# H0ARAx_Backend.net
KiCad netlist of a schematic drawn in Altium Designer
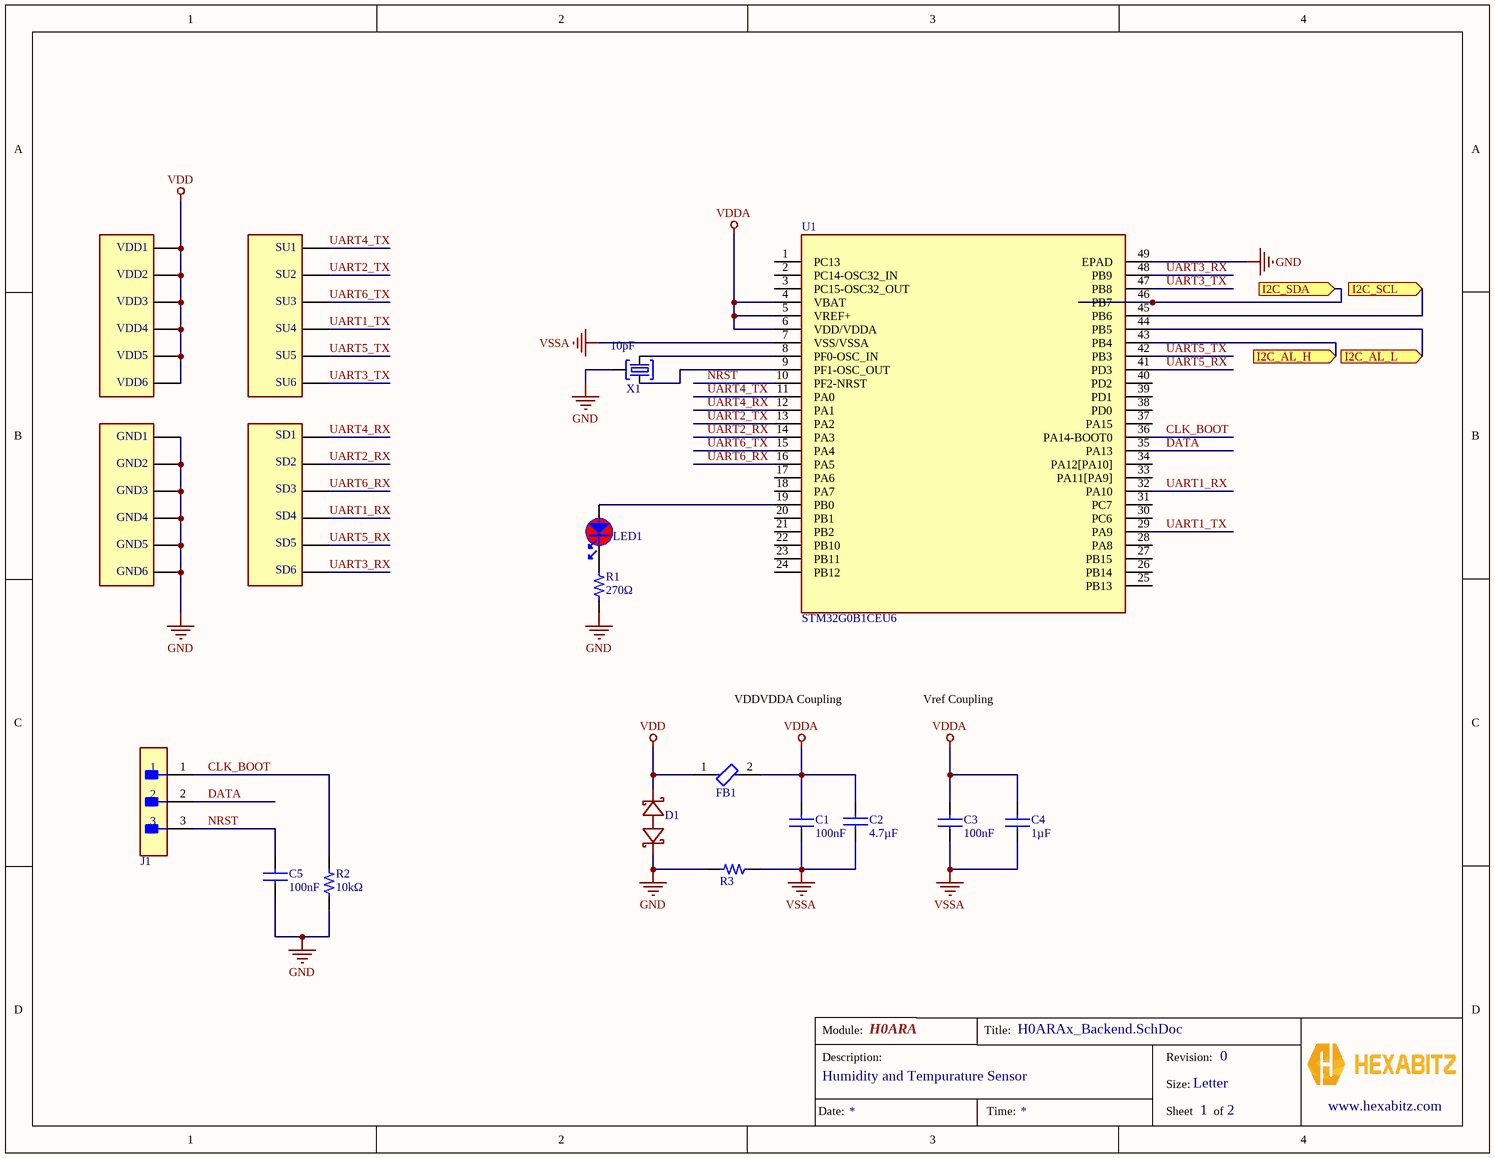
[diagram p0: H0ARAx_Backend.SchDoc]

(export (version "E")
  (design (tool "Eeschema 10.0.6"))
  (components
    (comp (ref "C1")
      (value "100nF")
      (footprint "C0603")
      (fields
        (field (name "MANUFACTURER") "Samsung Electro-Mechanics")
        (field (name "MANUFACTURER PART NUMBER") "CL10B104KA8NNNC")
        (field (name "TOLERANCE") "10%")
      )
      (libsource (lib "Hexabitz Altium Library") (part "generic Capacitor"))
    )
    (comp (ref "C2")
      (value "4.7µF")
      (footprint "C0805")
      (fields
        (field (name "MANUFACTURER") "Samsung Electro-Mechanics")
        (field (name "MANUFACTURER PART NUMBER") "CL21X475KAQNNNE")
        (field (name "TOLERANCE") "10%")
      )
      (libsource (lib "Hexabitz Altium Library") (part "generic Capacitor"))
    )
    (comp (ref "C3")
      (value "100nF")
      (footprint "C0603")
      (fields
        (field (name "MANUFACTURER") "Samsung Electro-Mechanics")
        (field (name "MANUFACTURER PART NUMBER") "CL10B104KA8NNNC")
        (field (name "TOLERANCE") "10%")
      )
      (libsource (lib "Hexabitz Altium Library") (part "generic Capacitor"))
    )
    (comp (ref "C4")
      (value "1µF")
      (footprint "C0805")
      (description "Ceramic Capacitor, Ceramic, 16V, 10% +Tol, 10% -Tol, X7R, 15% TC, 1uF, Surface Mount, 0805")
      (fields
        (field (name "MANUFACTURER") "Yageo Group")
        (field (name "MANUFACTURER PART NUMBER") "CC0805KKX7R7BB105")
      )
      (libsource (lib "Hexabitz Altium Library") (part "generic Capacitor"))
    )
    (comp (ref "C5")
      (value "100nF")
      (footprint "C0603")
      (fields
        (field (name "MANUFACTURER") "Samsung Electro-Mechanics")
        (field (name "MANUFACTURER PART NUMBER") "CL10B104KA8NNNC")
        (field (name "TOLERANCE") "10%")
      )
      (libsource (lib "Hexabitz Altium Library") (part "generic Capacitor"))
    )
    (comp (ref "D1")
      (value "CDSOD323-T03SC")
      (footprint "SOD2513X114N")
      (description "A 3V, 350W, bi-directional, standard capacitance, SOD323 pkg TVS Diode ¦ Bourns CDSOD323-T03SC")
      (fields (field (name "MANUFACTURER") "Bourns"))
      (libsource (lib "Hexabitz Altium Library") (part "CDSOD323-T03SC"))
    )
    (comp (ref "FB1")
      (value "MMZ1608Y300B")
      (footprint "FP-MMZ1608-0_8-MFG")
      (description "Ferrite Beads 0603 30ohms 1500mA Signal Line AEC-Q200")
      (fields
        (field (name "MANUFACTURER") "TDK")
        (field (name "MANUFACTURER PART NUMBER") "MMZ1608Y300BTD25")
      )
      (libsource (lib "Hexabitz Altium Library") (part "MMZ1608Y300B"))
    )
    (comp (ref "GND1")
      (value "HEXABIT_UART_PORT")
      (footprint "HEXABIT_POWER_PORT_D")
      (libsource (lib "hexabitz_connectors.Library") (part "HEXABIT_POWER_PORT_D"))
    )
    (comp (ref "GND2")
      (value "HEXABIT_UART_PORT")
      (footprint "HEXABIT_POWER_PORT_D")
      (libsource (lib "hexabitz_connectors.Library") (part "HEXABIT_POWER_PORT_D"))
    )
    (comp (ref "GND3")
      (value "HEXABIT_UART_PORT")
      (footprint "HEXABIT_POWER_PORT_D")
      (libsource (lib "hexabitz_connectors.Library") (part "HEXABIT_POWER_PORT_D"))
    )
    (comp (ref "GND4")
      (value "HEXABIT_UART_PORT")
      (footprint "HEXABIT_POWER_PORT_D")
      (libsource (lib "hexabitz_connectors.Library") (part "HEXABIT_POWER_PORT_D"))
    )
    (comp (ref "GND5")
      (value "HEXABIT_UART_PORT")
      (footprint "HEXABIT_POWER_PORT_D")
      (libsource (lib "hexabitz_connectors.Library") (part "HEXABIT_POWER_PORT_D"))
    )
    (comp (ref "GND6")
      (value "HEXABIT_UART_PORT")
      (footprint "HEXABIT_POWER_PORT_D")
      (libsource (lib "hexabitz_connectors.Library") (part "HEXABIT_POWER_PORT_D"))
    )
    (comp (ref "J1")
      (value "TSW-103-14-G-S")
      (footprint "FP-TSW-103-14-G-S-MFG")
      (description "CONN HEADER VERT 3POS 2.54MM")
      (libsource (lib "Altium Content Vault") (part "cd3439d6ef35ae5d9b27ec4fdd3e828"))
    )
    (comp (ref "LED1")
      (value "VLMS1300-GS08")
      (footprint "FP-6_541-5092_01-4-MFG")
      (description "LED Uni-Color Super Red 639nm 2-Pin Chip 0603(1608Metric) T/R")
      (fields (field (name "MANUFACTURER") "Vishay Semiconductors"))
      (libsource (lib "Hexabitz Altium Library") (part "VLMS1300-GS08"))
    )
    (comp (ref "R1")
      (value "270Ω")
      (footprint "R0603")
      (description "Res Thick Film 0603 270 Ohm 5% 0.1W(1/10W) ±200ppm/C Pad SMD Automotive T/R")
      (fields
        (field (name "MANUFACTURER") "Panasonic")
        (field (name "MANUFACTURER PART NUMBER") "ERJ-3GEYJ271V")
      )
      (libsource (lib "") (part "generic Resistor_1"))
    )
    (comp (ref "R2")
      (value "10kΩ")
      (footprint "R0603")
      (description "100mW Thick Film Resistors ±100ppm/℃ ±1% 10kΩ 0603 Chip Resistor - Surface Mount ROHS")
      (fields
        (field (name "MANUFACTURER") "Yageo Group")
        (field (name "MANUFACTURER PART NUMBER") "RC0603FR-0710KL")
      )
      (libsource (lib "") (part "generic Resistor_2"))
    )
    (comp (ref "R3")
      (value "Manufacturer Part Number")
      (footprint "R0603")
      (libsource (lib "Hexabitz Altium Library") (part "generic Resistor"))
    )
    (comp (ref "SD1")
      (value "HEXABIT_UART_PORT")
      (footprint "HEXABIT_UART_PORT_D")
      (libsource (lib "hexabitz_connectors.Library") (part "HEXABIT_UART_PORT_D"))
    )
    (comp (ref "SD2")
      (value "HEXABIT_UART_PORT")
      (footprint "HEXABIT_UART_PORT_D")
      (libsource (lib "hexabitz_connectors.Library") (part "HEXABIT_UART_PORT_D"))
    )
    (comp (ref "SD3")
      (value "HEXABIT_UART_PORT")
      (footprint "HEXABIT_UART_PORT_D")
      (libsource (lib "hexabitz_connectors.Library") (part "HEXABIT_UART_PORT_D"))
    )
    (comp (ref "SD4")
      (value "HEXABIT_UART_PORT")
      (footprint "HEXABIT_UART_PORT_D")
      (libsource (lib "hexabitz_connectors.Library") (part "HEXABIT_UART_PORT_D"))
    )
    (comp (ref "SD5")
      (value "HEXABIT_UART_PORT")
      (footprint "HEXABIT_UART_PORT_D")
      (libsource (lib "hexabitz_connectors.Library") (part "HEXABIT_UART_PORT_D"))
    )
    (comp (ref "SD6")
      (value "HEXABIT_UART_PORT")
      (footprint "HEXABIT_UART_PORT_D")
      (libsource (lib "hexabitz_connectors.Library") (part "HEXABIT_UART_PORT_D"))
    )
    (comp (ref "SU1")
      (value "HEXABIT_UART_PORT")
      (footprint "HEXABIT_UART_PORT_U")
      (libsource (lib "hexabitz_connectors.Library") (part "HEXABIT_UART_PORT_U"))
    )
    (comp (ref "SU2")
      (value "HEXABIT_UART_PORT")
      (footprint "HEXABIT_UART_PORT_U")
      (libsource (lib "hexabitz_connectors.Library") (part "HEXABIT_UART_PORT_U"))
    )
    (comp (ref "SU3")
      (value "HEXABIT_UART_PORT")
      (footprint "HEXABIT_UART_PORT_U")
      (libsource (lib "hexabitz_connectors.Library") (part "HEXABIT_UART_PORT_U"))
    )
    (comp (ref "SU4")
      (value "HEXABIT_UART_PORT")
      (footprint "HEXABIT_UART_PORT_U")
      (libsource (lib "hexabitz_connectors.Library") (part "HEXABIT_UART_PORT_U"))
    )
    (comp (ref "SU5")
      (value "HEXABIT_UART_PORT")
      (footprint "HEXABIT_UART_PORT_U")
      (libsource (lib "hexabitz_connectors.Library") (part "HEXABIT_UART_PORT_U"))
    )
    (comp (ref "SU6")
      (value "HEXABIT_UART_PORT")
      (footprint "HEXABIT_UART_PORT_U")
      (libsource (lib "hexabitz_connectors.Library") (part "HEXABIT_UART_PORT_U"))
    )
    (comp (ref "U1")
      (value "STM32G0B1CEU6")
      (footprint "QFN50P700X700X65-49N-D")
      (description "MCU 32-bit ARM Cortex M0+ RISC 512KB Flash 1.8V/2.5V/3.3V 48-Pin UFQFPN EP Tray")
      (fields
        (field (name "MANUFACTURER") "STMicroelectronics")
        (field (name "MANUFACTURER PART NUMBER") "STM32G0B1CEU6")
      )
      (libsource (lib "Hexabitz Altium Library") (part "STM32G0B1CEU6"))
    )
    (comp (ref "VDD1")
      (value "HEXABIT_UART_PORT")
      (footprint "HEXABIT_POWER_PORT_U")
      (libsource (lib "hexabitz_connectors.Library") (part "HEXABIT_POWER_PORT_U"))
    )
    (comp (ref "VDD2")
      (value "HEXABIT_UART_PORT")
      (footprint "HEXABIT_POWER_PORT_U")
      (libsource (lib "hexabitz_connectors.Library") (part "HEXABIT_POWER_PORT_U"))
    )
    (comp (ref "VDD3")
      (value "HEXABIT_UART_PORT")
      (footprint "HEXABIT_POWER_PORT_U")
      (libsource (lib "hexabitz_connectors.Library") (part "HEXABIT_POWER_PORT_U"))
    )
    (comp (ref "VDD4")
      (value "HEXABIT_UART_PORT")
      (footprint "HEXABIT_POWER_PORT_U")
      (libsource (lib "hexabitz_connectors.Library") (part "HEXABIT_POWER_PORT_U"))
    )
    (comp (ref "VDD5")
      (value "HEXABIT_UART_PORT")
      (footprint "HEXABIT_POWER_PORT_U")
      (libsource (lib "hexabitz_connectors.Library") (part "HEXABIT_POWER_PORT_U"))
    )
    (comp (ref "VDD6")
      (value "HEXABIT_UART_PORT")
      (footprint "HEXABIT_POWER_PORT_U")
      (libsource (lib "hexabitz_connectors.Library") (part "HEXABIT_POWER_PORT_U"))
    )
    (comp (ref "X1")
      (value "10pF")
      (footprint "XTALL_CSTCE8M00G52")
      (description "Ceramic Resonator 8MHz ±0.5% (Tol) ±0.2% (Stability) 10pF 40Ohm 3-Pin CSMD T/R")
      (fields
        (field (name "MANUFACTURER") "Murata")
        (field (name "MANUFACTURER PART NUMBER") "CSTCE8M00G52Z-R0")
      )
      (libsource (lib "Hexabitz Altium Library") (part "CSTCE8M00G52Z-R0"))
    )
  )
  (nets
    (net (code "1") (name "/CLK_BOOT") (class "Default")
      (node (ref "J1") (pin "1") (pinfunction "1_1") (pintype "passive"))
      (node (ref "R2") (pin "1") (pinfunction "1_1") (pintype "passive"))
      (node (ref "U1") (pin "36") (pinfunction "PA14-BOOT0_36") (pintype "passive"))
    )
    (net (code "2") (name "/DATA") (class "Default")
      (node (ref "J1") (pin "2") (pinfunction "2_2") (pintype "passive"))
      (node (ref "U1") (pin "35") (pinfunction "PA13_35") (pintype "passive"))
    )
    (net (code "3") (name "/I2C_AL_H") (class "Default")
      (node (ref "U1") (pin "43") (pinfunction "PB4_43") (pintype "passive"))
    )
    (net (code "4") (name "/I2C_AL_L") (class "Default")
      (node (ref "U1") (pin "44") (pinfunction "PB5_44") (pintype "passive"))
    )
    (net (code "5") (name "/I2C_SCL") (class "Default")
      (node (ref "U1") (pin "45") (pinfunction "PB6_45") (pintype "passive"))
    )
    (net (code "6") (name "/I2C_SDA") (class "Default")
      (node (ref "U1") (pin "46") (pinfunction "PB7_46") (pintype "passive"))
    )
    (net (code "7") (name "/NRST") (class "Default")
      (node (ref "C5") (pin "2") (pinfunction "2_2") (pintype "passive"))
      (node (ref "J1") (pin "3") (pinfunction "3_3") (pintype "passive"))
      (node (ref "U1") (pin "10") (pinfunction "PF2-NRST_10") (pintype "passive"))
    )
    (net (code "8") (name "/UART1_RX") (class "Default")
      (node (ref "SD4") (pin "UART_D") (pinfunction "UART_D_UART_D") (pintype "passive"))
      (node (ref "U1") (pin "32") (pinfunction "PA10_32") (pintype "passive"))
    )
    (net (code "9") (name "/UART1_TX") (class "Default")
      (node (ref "SU4") (pin "UART_U") (pinfunction "UART_U_UART_U") (pintype "passive"))
      (node (ref "U1") (pin "29") (pinfunction "PA9_29") (pintype "passive"))
    )
    (net (code "10") (name "/UART2_RX") (class "Default")
      (node (ref "SD2") (pin "UART_D") (pinfunction "UART_D_UART_D") (pintype "passive"))
      (node (ref "U1") (pin "14") (pinfunction "PA3_14") (pintype "passive"))
    )
    (net (code "11") (name "/UART2_TX") (class "Default")
      (node (ref "SU2") (pin "UART_U") (pinfunction "UART_U_UART_U") (pintype "passive"))
      (node (ref "U1") (pin "13") (pinfunction "PA2_13") (pintype "passive"))
    )
    (net (code "12") (name "/UART3_RX") (class "Default")
      (node (ref "SD6") (pin "UART_D") (pinfunction "UART_D_UART_D") (pintype "passive"))
      (node (ref "U1") (pin "48") (pinfunction "PB9_48") (pintype "passive"))
    )
    (net (code "13") (name "/UART3_TX") (class "Default")
      (node (ref "SU6") (pin "UART_U") (pinfunction "UART_U_UART_U") (pintype "passive"))
      (node (ref "U1") (pin "47") (pinfunction "PB8_47") (pintype "passive"))
    )
    (net (code "14") (name "/UART4_RX") (class "Default")
      (node (ref "SD1") (pin "UART_D") (pinfunction "UART_D_UART_D") (pintype "passive"))
      (node (ref "U1") (pin "12") (pinfunction "PA1_12") (pintype "passive"))
    )
    (net (code "15") (name "/UART4_TX") (class "Default")
      (node (ref "SU1") (pin "UART_U") (pinfunction "UART_U_UART_U") (pintype "passive"))
      (node (ref "U1") (pin "11") (pinfunction "PA0_11") (pintype "passive"))
    )
    (net (code "16") (name "/UART5_RX") (class "Default")
      (node (ref "SD5") (pin "UART_D") (pinfunction "UART_D_UART_D") (pintype "passive"))
      (node (ref "U1") (pin "41") (pinfunction "PD3_41") (pintype "passive"))
    )
    (net (code "17") (name "/UART5_TX") (class "Default")
      (node (ref "SU5") (pin "UART_U") (pinfunction "UART_U_UART_U") (pintype "passive"))
      (node (ref "U1") (pin "42") (pinfunction "PB3_42") (pintype "passive"))
    )
    (net (code "18") (name "/UART6_RX") (class "Default")
      (node (ref "SD3") (pin "UART_D") (pinfunction "UART_D_UART_D") (pintype "passive"))
      (node (ref "U1") (pin "16") (pinfunction "PA5_16") (pintype "passive"))
    )
    (net (code "19") (name "/UART6_TX") (class "Default")
      (node (ref "SU3") (pin "UART_U") (pinfunction "UART_U_UART_U") (pintype "passive"))
      (node (ref "U1") (pin "15") (pinfunction "PA4_15") (pintype "passive"))
    )
    (net (code "20") (name "GND") (class "Default")
      (node (ref "C5") (pin "1") (pinfunction "1_1") (pintype "passive"))
      (node (ref "D1") (pin "1") (pinfunction "A_1") (pintype "passive"))
      (node (ref "GND1") (pin "Pwr_D") (pinfunction "Pwr_D_Pwr_D") (pintype "passive"))
      (node (ref "GND2") (pin "Pwr_D") (pinfunction "Pwr_D_Pwr_D") (pintype "passive"))
      (node (ref "GND3") (pin "Pwr_D") (pinfunction "Pwr_D_Pwr_D") (pintype "passive"))
      (node (ref "GND4") (pin "Pwr_D") (pinfunction "Pwr_D_Pwr_D") (pintype "passive"))
      (node (ref "GND5") (pin "Pwr_D") (pinfunction "Pwr_D_Pwr_D") (pintype "passive"))
      (node (ref "GND6") (pin "Pwr_D") (pinfunction "Pwr_D_Pwr_D") (pintype "passive"))
      (node (ref "R1") (pin "1") (pinfunction "1_1") (pintype "passive"))
      (node (ref "R2") (pin "2") (pinfunction "2_2") (pintype "passive"))
      (node (ref "R3") (pin "1") (pinfunction "1_1") (pintype "passive"))
      (node (ref "U1") (pin "49") (pinfunction "EPAD_49") (pintype "passive"))
      (node (ref "X1") (pin "P$2") (pinfunction "2_P$2") (pintype "passive"))
    )
    (net (code "21") (name "Net-(LED1-Pad1)") (class "Default")
      (node (ref "LED1") (pin "1") (pintype "passive"))
      (node (ref "R1") (pin "2") (pinfunction "2_2") (pintype "passive"))
    )
    (net (code "22") (name "Net-(U1-PB0)") (class "Default")
      (node (ref "LED1") (pin "2") (pintype "passive"))
      (node (ref "U1") (pin "19") (pinfunction "PB0_19") (pintype "passive"))
    )
    (net (code "23") (name "Net-(U1-PF0-OSC_IN)") (class "Default")
      (node (ref "U1") (pin "8") (pinfunction "PF0-OSC_IN_8") (pintype "passive"))
      (node (ref "X1") (pin "P$3") (pinfunction "3_P$3") (pintype "passive"))
    )
    (net (code "24") (name "Net-(U1-PF1-OSC_OUT)") (class "Default")
      (node (ref "U1") (pin "9") (pinfunction "PF1-OSC_OUT_9") (pintype "passive"))
      (node (ref "X1") (pin "P$1") (pinfunction "1_P$1") (pintype "passive"))
    )
    (net (code "25") (name "VDD") (class "Default")
      (node (ref "D1") (pin "2") (pinfunction "C_2") (pintype "passive"))
      (node (ref "FB1") (pin "1") (pinfunction "1_1") (pintype "passive"))
      (node (ref "VDD1") (pin "Pwr_U") (pinfunction "Pwr_U_Pwr_U") (pintype "passive"))
      (node (ref "VDD2") (pin "Pwr_U") (pinfunction "Pwr_U_Pwr_U") (pintype "passive"))
      (node (ref "VDD3") (pin "Pwr_U") (pinfunction "Pwr_U_Pwr_U") (pintype "passive"))
      (node (ref "VDD4") (pin "Pwr_U") (pinfunction "Pwr_U_Pwr_U") (pintype "passive"))
      (node (ref "VDD5") (pin "Pwr_U") (pinfunction "Pwr_U_Pwr_U") (pintype "passive"))
      (node (ref "VDD6") (pin "Pwr_U") (pinfunction "Pwr_U_Pwr_U") (pintype "passive"))
    )
    (net (code "26") (name "VDDA") (class "Default")
      (node (ref "C1") (pin "2") (pinfunction "2_2") (pintype "passive"))
      (node (ref "C2") (pin "1") (pinfunction "1_1") (pintype "passive"))
      (node (ref "C3") (pin "2") (pinfunction "2_2") (pintype "passive"))
      (node (ref "C4") (pin "2") (pinfunction "2_2") (pintype "passive"))
      (node (ref "FB1") (pin "2") (pinfunction "2_2") (pintype "passive"))
      (node (ref "U1") (pin "4") (pinfunction "VBAT_4") (pintype "passive"))
      (node (ref "U1") (pin "5") (pinfunction "VREF+_5") (pintype "passive"))
      (node (ref "U1") (pin "6") (pinfunction "VDD/VDDA_6") (pintype "passive"))
    )
    (net (code "27") (name "VSSA") (class "Default")
      (node (ref "C1") (pin "1") (pinfunction "1_1") (pintype "passive"))
      (node (ref "C2") (pin "2") (pinfunction "2_2") (pintype "passive"))
      (node (ref "C3") (pin "1") (pinfunction "1_1") (pintype "passive"))
      (node (ref "C4") (pin "1") (pinfunction "1_1") (pintype "passive"))
      (node (ref "R3") (pin "2") (pinfunction "2_2") (pintype "passive"))
      (node (ref "U1") (pin "7") (pinfunction "VSS/VSSA_7") (pintype "passive"))
    )
    (net (code "28") (name "unconnected-(U1-PA6-Pad17)") (class "Default")
      (node (ref "U1") (pin "17") (pinfunction "PA6_17") (pintype "passive"))
    )
    (net (code "29") (name "unconnected-(U1-PA7-Pad18)") (class "Default")
      (node (ref "U1") (pin "18") (pinfunction "PA7_18") (pintype "passive"))
    )
    (net (code "30") (name "unconnected-(U1-PA8-Pad28)") (class "Default")
      (node (ref "U1") (pin "28") (pinfunction "PA8_28") (pintype "passive"))
    )
    (net (code "31") (name "unconnected-(U1-PA11[PA9]-Pad33)") (class "Default")
      (node (ref "U1") (pin "33") (pinfunction "PA11[PA9]_33") (pintype "passive"))
    )
    (net (code "32") (name "unconnected-(U1-PA12[PA10]-Pad34)") (class "Default")
      (node (ref "U1") (pin "34") (pinfunction "PA12[PA10]_34") (pintype "passive"))
    )
    (net (code "33") (name "unconnected-(U1-PA15-Pad37)") (class "Default")
      (node (ref "U1") (pin "37") (pinfunction "PA15_37") (pintype "passive"))
    )
    (net (code "34") (name "unconnected-(U1-PB1-Pad20)") (class "Default")
      (node (ref "U1") (pin "20") (pinfunction "PB1_20") (pintype "passive"))
    )
    (net (code "35") (name "unconnected-(U1-PB2-Pad21)") (class "Default")
      (node (ref "U1") (pin "21") (pinfunction "PB2_21") (pintype "passive"))
    )
    (net (code "36") (name "unconnected-(U1-PB10-Pad22)") (class "Default")
      (node (ref "U1") (pin "22") (pinfunction "PB10_22") (pintype "passive"))
    )
    (net (code "37") (name "unconnected-(U1-PB11-Pad23)") (class "Default")
      (node (ref "U1") (pin "23") (pinfunction "PB11_23") (pintype "passive"))
    )
    (net (code "38") (name "unconnected-(U1-PB12-Pad24)") (class "Default")
      (node (ref "U1") (pin "24") (pinfunction "PB12_24") (pintype "passive"))
    )
    (net (code "39") (name "unconnected-(U1-PB13-Pad25)") (class "Default")
      (node (ref "U1") (pin "25") (pinfunction "PB13_25") (pintype "passive"))
    )
    (net (code "40") (name "unconnected-(U1-PB14-Pad26)") (class "Default")
      (node (ref "U1") (pin "26") (pinfunction "PB14_26") (pintype "passive"))
    )
    (net (code "41") (name "unconnected-(U1-PB15-Pad27)") (class "Default")
      (node (ref "U1") (pin "27") (pinfunction "PB15_27") (pintype "passive"))
    )
    (net (code "42") (name "unconnected-(U1-PC6-Pad30)") (class "Default")
      (node (ref "U1") (pin "30") (pinfunction "PC6_30") (pintype "passive"))
    )
    (net (code "43") (name "unconnected-(U1-PC7-Pad31)") (class "Default")
      (node (ref "U1") (pin "31") (pinfunction "PC7_31") (pintype "passive"))
    )
    (net (code "44") (name "unconnected-(U1-PC13-Pad1)") (class "Default")
      (node (ref "U1") (pin "1") (pinfunction "PC13_1") (pintype "passive"))
    )
    (net (code "45") (name "unconnected-(U1-PC14-OSC32_IN-Pad2)") (class "Default")
      (node (ref "U1") (pin "2") (pinfunction "PC14-OSC32_IN_2") (pintype "passive"))
    )
    (net (code "46") (name "unconnected-(U1-PC15-OSC32_OUT-Pad3)") (class "Default")
      (node (ref "U1") (pin "3") (pinfunction "PC15-OSC32_OUT_3") (pintype "passive"))
    )
    (net (code "47") (name "unconnected-(U1-PD0-Pad38)") (class "Default")
      (node (ref "U1") (pin "38") (pinfunction "PD0_38") (pintype "passive"))
    )
    (net (code "48") (name "unconnected-(U1-PD1-Pad39)") (class "Default")
      (node (ref "U1") (pin "39") (pinfunction "PD1_39") (pintype "passive"))
    )
    (net (code "49") (name "unconnected-(U1-PD2-Pad40)") (class "Default")
      (node (ref "U1") (pin "40") (pinfunction "PD2_40") (pintype "passive"))
    )
  )
)
